# LiDAR_Lite_Interface_CAN.net
KiCad netlist of a schematic drawn in EAGLE
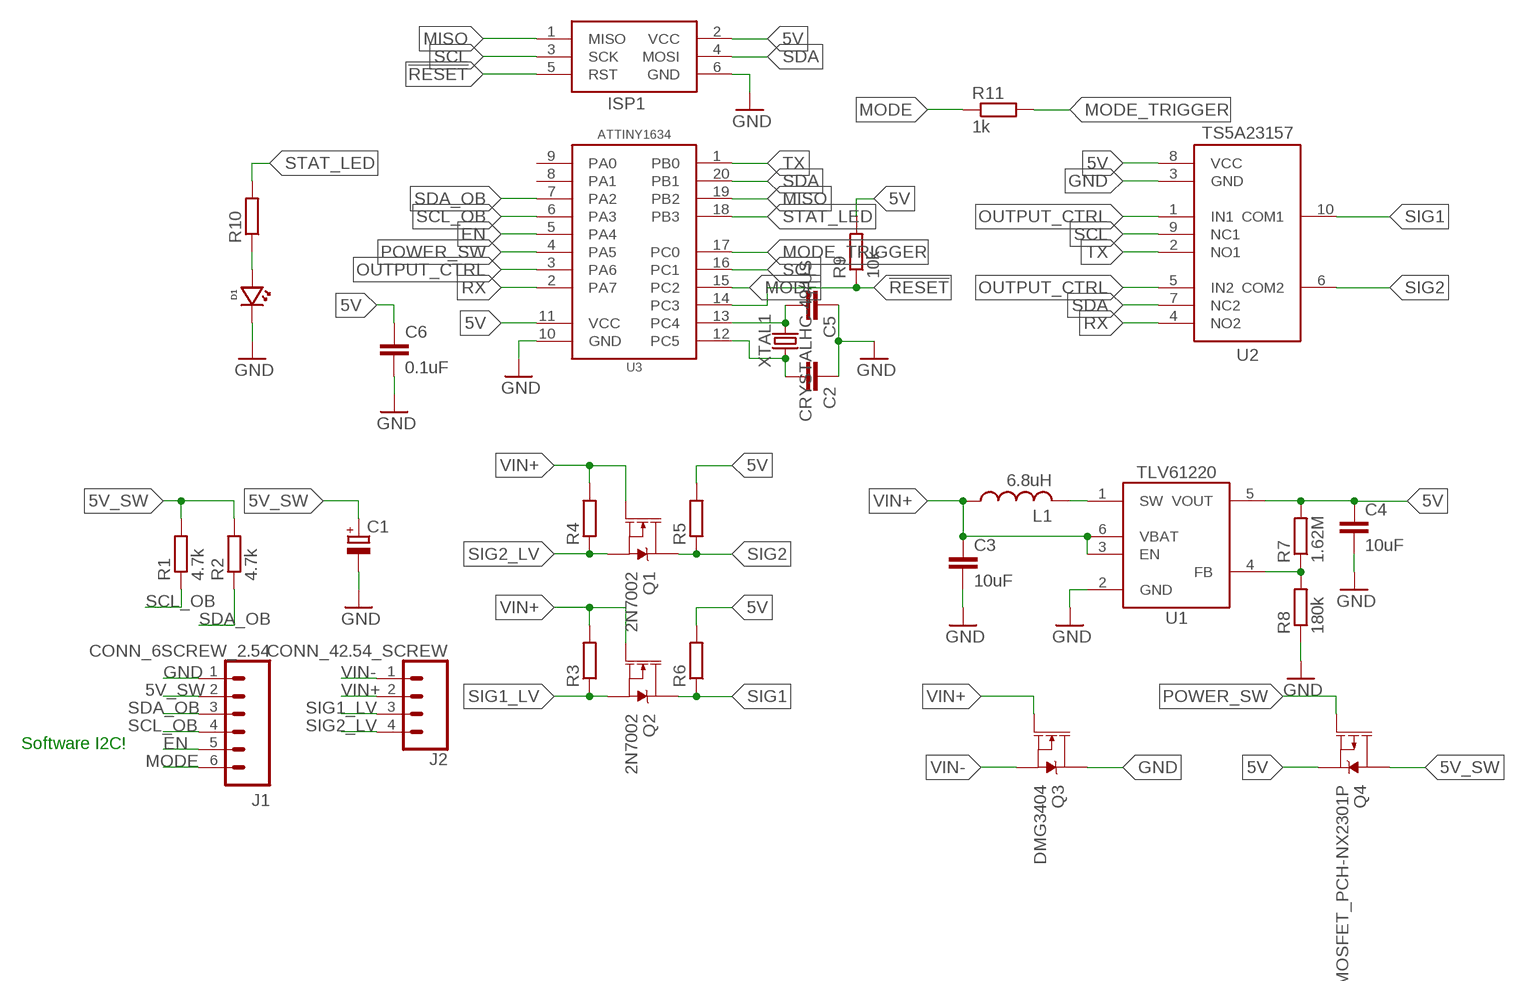
[diagram p0: schematic, sheet 1]

(export (version "E")
  (design (tool "Eeschema 10.0.6"))
  (components
    (comp (ref "C1")
      (value "CPOL-EUUW-10X10")
      (footprint "eagle-import:UW-10X10_NICHICON")
      (libsource (lib "eagle-import") (part "CPOL-EUUW-10X10"))
    )
    (comp (ref "C2")
      (value "C-EU10PFC0603")
      (footprint "eagle-import:C0603")
      (fields (field (name "MF") "Yageo") (field (name "MPN") "CC0603JRNPO9BN100CC0603JRNPO9BN100"))
      (libsource (lib "eagle-import") (part "C-EUC060310PF"))
    )
    (comp (ref "C3")
      (value "10uF")
      (footprint "eagle-import:C0805")
      (fields (field (name "MF") "Murata") (field (name "MPN") "GRM21BR61C106KE15K"))
      (libsource (lib "eagle-import") (part "C-EUC080510UF"))
    )
    (comp (ref "C4")
      (value "10uF")
      (footprint "eagle-import:C0805")
      (fields (field (name "MF") "Murata") (field (name "MPN") "GRM21BR61C106KE15K"))
      (libsource (lib "eagle-import") (part "C-EUC080510UF"))
    )
    (comp (ref "C5")
      (value "C-EU10PFC0603")
      (footprint "eagle-import:C0603")
      (fields (field (name "MF") "Yageo") (field (name "MPN") "CC0603JRNPO9BN100CC0603JRNPO9BN100"))
      (libsource (lib "eagle-import") (part "C-EUC060310PF"))
    )
    (comp (ref "C6")
      (value "0.1uF")
      (footprint "eagle-import:C0603")
      (fields (field (name "MF") "Murata") (field (name "MPN") "GCM188R71E104KA57D"))
      (libsource (lib "eagle-import") (part "C-EUC06030.1UF"))
    )
    (comp (ref "D1")
      (value "LED0603")
      (footprint "eagle-import:LED_0603")
      (libsource (lib "eagle-import") (part "LED0603"))
    )
    (comp (ref "ISP1")
      (value "AVRISP-6")
      (footprint "eagle-import:AVRISP")
      (libsource (lib "eagle-import") (part "AVRISP-6"))
    )
    (comp (ref "J1")
      (value "CONN_6SCREW_2.54")
      (footprint "eagle-import:1X06_SCREW")
      (fields (field (name "MF") "OnShore") (field (name "MPN") "OSTVN06A150"))
      (libsource (lib "eagle-import") (part "CONN_6SCREW_2.54"))
    )
    (comp (ref "J2")
      (value "CONN_42.54_SCREW")
      (footprint "eagle-import:1X04_SCREW")
      (fields (field (name "MF") "On Shore") (field (name "MPN") "OSTVN04A150"))
      (libsource (lib "eagle-import") (part "CONN_42.54_SCREW"))
    )
    (comp (ref "L1")
      (value "6.8uH")
      (footprint "eagle-import:1008")
      (fields (field (name "MF") "Wurth") (field (name "MPN") "74438323068"))
      (libsource (lib "eagle-import") (part "INDUCTOR1008"))
    )
    (comp (ref "Q1")
      (value "2N7002")
      (footprint "eagle-import:SOT23-3")
      (fields (field (name "MF") "Nexperia") (field (name "MPN") "2N7002P,215"))
      (libsource (lib "eagle-import") (part "MOSFET-NCH-2N7002P"))
    )
    (comp (ref "Q2")
      (value "2N7002")
      (footprint "eagle-import:SOT23-3")
      (fields (field (name "MF") "Nexperia") (field (name "MPN") "2N7002P,215"))
      (libsource (lib "eagle-import") (part "MOSFET-NCH-2N7002P"))
    )
    (comp (ref "Q3")
      (value "DMG3404")
      (footprint "eagle-import:SOT23-3")
      (fields (field (name "MF") "Diodes Incorporated") (field (name "MPN") "DMG3404L-7"))
      (libsource (lib "eagle-import") (part "MOSFET-NCH-DMG3404L"))
    )
    (comp (ref "Q4")
      (value "MOSFET_PCH-NX2301P")
      (footprint "eagle-import:SOT23-3")
      (fields (field (name "MF") "Nexperia") (field (name "MPN") "NX2301P,215"))
      (libsource (lib "eagle-import") (part "MOSFET_PCH-NX2301P"))
    )
    (comp (ref "R1")
      (value "4.7k")
      (footprint "eagle-import:R0603")
      (fields (field (name "MF") "Yageo") (field (name "MPN") "RC0603FR-074K7L"))
      (libsource (lib "eagle-import") (part "R-EU_R06034.7K"))
    )
    (comp (ref "R2")
      (value "4.7k")
      (footprint "eagle-import:R0603")
      (fields (field (name "MF") "Yageo") (field (name "MPN") "RC0603FR-074K7L"))
      (libsource (lib "eagle-import") (part "R-EU_R06034.7K"))
    )
    (comp (ref "R3")
      (value "R-EU_10KR0603")
      (footprint "eagle-import:R0603")
      (fields
        (field (name "MF") "Yageo")
        (field (name "MPN") "RC0603FR-0710KL")
        (field (name "VALUE_PART") "10k")
      )
      (libsource (lib "eagle-import") (part "R-EU_R060310K"))
    )
    (comp (ref "R4")
      (value "R-EU_10KR0603")
      (footprint "eagle-import:R0603")
      (fields
        (field (name "MF") "Yageo")
        (field (name "MPN") "RC0603FR-0710KL")
        (field (name "VALUE_PART") "10k")
      )
      (libsource (lib "eagle-import") (part "R-EU_R060310K"))
    )
    (comp (ref "R5")
      (value "R-EU_10KR0603")
      (footprint "eagle-import:R0603")
      (fields
        (field (name "MF") "Yageo")
        (field (name "MPN") "RC0603FR-0710KL")
        (field (name "VALUE_PART") "10k")
      )
      (libsource (lib "eagle-import") (part "R-EU_R060310K"))
    )
    (comp (ref "R6")
      (value "R-EU_10KR0603")
      (footprint "eagle-import:R0603")
      (fields
        (field (name "MF") "Yageo")
        (field (name "MPN") "RC0603FR-0710KL")
        (field (name "VALUE_PART") "10k")
      )
      (libsource (lib "eagle-import") (part "R-EU_R060310K"))
    )
    (comp (ref "R7")
      (value "1.62M")
      (footprint "eagle-import:R0603")
      (fields (field (name "MF") "Stackpole") (field (name "MPN") "RMCF0603FT1M62"))
      (libsource (lib "eagle-import") (part "R-EU_R06031.62M"))
    )
    (comp (ref "R8")
      (value "180k")
      (footprint "eagle-import:R0603")
      (fields (field (name "MF") "Panasonic") (field (name "MPN") "ERJ-3EKF1803V"))
      (libsource (lib "eagle-import") (part "R-EU_R0603180K"))
    )
    (comp (ref "R9")
      (value "10k")
      (footprint "eagle-import:R0603")
      (fields (field (name "MF") "Yageo") (field (name "MPN") "RC0603FR-0710KL"))
      (libsource (lib "eagle-import") (part "R-EU_R060310K"))
    )
    (comp (ref "R10")
      (value "R-EU_330R0603")
      (footprint "eagle-import:R0603")
      (fields
        (field (name "MF") "Yageo")
        (field (name "MPN") "RC0603FR-07330RL")
        (field (name "VALUE_PART") "330")
      )
      (libsource (lib "eagle-import") (part "R-EU_R0603330"))
    )
    (comp (ref "R11")
      (value "1k")
      (footprint "eagle-import:R0603")
      (fields (field (name "MF") "Yageo") (field (name "MPN") "AC0603FR-071KL"))
      (libsource (lib "eagle-import") (part "R-EU_R06031K"))
    )
    (comp (ref "U1")
      (value "TLV61220DBV")
      (footprint "eagle-import:DBV_R-PDSO-G6")
      (fields (field (name "MF") "TI") (field (name "MPN") "TLV61220DBVR"))
      (libsource (lib "eagle-import") (part "TLV61220DBV"))
    )
    (comp (ref "U2")
      (value "TS5A23157DGS")
      (footprint "eagle-import:DGS0010A")
      (fields (field (name "DISP") "TS5A23157") (field (name "MF") "TI") (field (name "MPN") "TS5A23157DGSR"))
      (libsource (lib "eagle-import") (part "TS5A23157DGS"))
    )
    (comp (ref "U3")
      (value "ATTINY1634SOIC")
      (footprint "eagle-import:SO-20DW")
      (fields (field (name "MF") "Atmel") (field (name "MPN") "ATTINY1634-SUR"))
      (libsource (lib "eagle-import") (part "ATTINY1634SOIC"))
    )
    (comp (ref "XTAL1")
      (value "CRYSTALHC-49/US")
      (footprint "eagle-import:HC49UP")
      (libsource (lib "eagle-import") (part "CRYSTALHC-49/US"))
    )
  )
  (nets
    (net (code "1") (name "/~{RESET}") (class "Default")
      (node (ref "ISP1") (pin "5") (pinfunction "RST_5") (pintype "output"))
      (node (ref "R9") (pin "1") (pinfunction "1_1") (pintype "passive"))
      (node (ref "U3") (pin "14") (pinfunction "PC3_14") (pintype "bidirectional"))
    )
    (net (code "2") (name "5V") (class "Default")
      (node (ref "C4") (pin "1") (pinfunction "1_1") (pintype "passive"))
      (node (ref "C6") (pin "1") (pinfunction "1_1") (pintype "passive"))
      (node (ref "ISP1") (pin "2") (pinfunction "VCC_2") (pintype "power_in"))
      (node (ref "Q4") (pin "2") (pinfunction "S_2") (pintype "bidirectional"))
      (node (ref "R5") (pin "2") (pinfunction "2_2") (pintype "passive"))
      (node (ref "R6") (pin "2") (pinfunction "2_2") (pintype "passive"))
      (node (ref "R7") (pin "2") (pinfunction "2_2") (pintype "passive"))
      (node (ref "R9") (pin "2") (pinfunction "2_2") (pintype "passive"))
      (node (ref "U1") (pin "5") (pinfunction "VOUT_5") (pintype "power_in"))
      (node (ref "U2") (pin "8") (pinfunction "VCC_8") (pintype "power_in"))
      (node (ref "U3") (pin "11") (pinfunction "VCC_11") (pintype "power_in"))
    )
    (net (code "3") (name "5V_SW") (class "Default")
      (node (ref "C1") (pin "+") (pinfunction "+_+") (pintype "passive"))
      (node (ref "J1") (pin "2") (pinfunction "2_2") (pintype "passive"))
      (node (ref "Q4") (pin "3") (pinfunction "D_3") (pintype "bidirectional"))
      (node (ref "R1") (pin "2") (pinfunction "2_2") (pintype "passive"))
      (node (ref "R2") (pin "2") (pinfunction "2_2") (pintype "passive"))
    )
    (net (code "4") (name "EN") (class "Default")
      (node (ref "J1") (pin "5") (pinfunction "5_5") (pintype "passive"))
      (node (ref "U3") (pin "5") (pinfunction "PA4_5") (pintype "bidirectional"))
    )
    (net (code "5") (name "GND") (class "Default")
      (node (ref "C1") (pin "-") (pinfunction "-_-") (pintype "passive"))
      (node (ref "C2") (pin "1") (pinfunction "1_1") (pintype "passive"))
      (node (ref "C3") (pin "2") (pinfunction "2_2") (pintype "passive"))
      (node (ref "C4") (pin "2") (pinfunction "2_2") (pintype "passive"))
      (node (ref "C5") (pin "1") (pinfunction "1_1") (pintype "passive"))
      (node (ref "C6") (pin "2") (pinfunction "2_2") (pintype "passive"))
      (node (ref "D1") (pin "CATHODE") (pinfunction "CATHODE_CATHODE") (pintype "power_in"))
      (node (ref "ISP1") (pin "6") (pinfunction "GND_6") (pintype "power_in"))
      (node (ref "J1") (pin "1") (pinfunction "1_1") (pintype "passive"))
      (node (ref "Q3") (pin "3") (pinfunction "D_3") (pintype "bidirectional"))
      (node (ref "R8") (pin "1") (pinfunction "1_1") (pintype "passive"))
      (node (ref "U1") (pin "2") (pinfunction "GND_2") (pintype "power_in"))
      (node (ref "U2") (pin "3") (pinfunction "GND_3") (pintype "power_in"))
      (node (ref "U3") (pin "10") (pinfunction "GND_10") (pintype "power_in"))
    )
    (net (code "6") (name "MISO") (class "Default")
      (node (ref "ISP1") (pin "1") (pinfunction "MISO_1") (pintype "input"))
      (node (ref "U3") (pin "19") (pinfunction "PB2_19") (pintype "bidirectional"))
    )
    (net (code "7") (name "MODE") (class "Default")
      (node (ref "J1") (pin "6") (pinfunction "6_6") (pintype "passive"))
      (node (ref "R11") (pin "1") (pinfunction "1_1") (pintype "passive"))
      (node (ref "U3") (pin "15") (pinfunction "PC2_15") (pintype "bidirectional"))
    )
    (net (code "8") (name "MODE_TRIGGER") (class "Default")
      (node (ref "R11") (pin "2") (pinfunction "2_2") (pintype "passive"))
      (node (ref "U3") (pin "17") (pinfunction "PC0_17") (pintype "bidirectional"))
    )
    (net (code "9") (name "Net-(D1-PadANODE)") (class "Default")
      (node (ref "D1") (pin "ANODE") (pinfunction "ANODE_ANODE") (pintype "power_in"))
      (node (ref "R10") (pin "1") (pinfunction "1_1") (pintype "passive"))
    )
    (net (code "10") (name "Net-(U1-FB)") (class "Default")
      (node (ref "R7") (pin "1") (pinfunction "1_1") (pintype "passive"))
      (node (ref "R8") (pin "2") (pinfunction "2_2") (pintype "passive"))
      (node (ref "U1") (pin "4") (pinfunction "FB_4") (pintype "input"))
    )
    (net (code "11") (name "Net-(U1-SW)") (class "Default")
      (node (ref "L1") (pin "2") (pinfunction "2_2") (pintype "passive"))
      (node (ref "U1") (pin "1") (pinfunction "SW_1") (pintype "power_in"))
    )
    (net (code "12") (name "Net-(U3-PC4)") (class "Default")
      (node (ref "C5") (pin "2") (pinfunction "2_2") (pintype "passive"))
      (node (ref "U3") (pin "13") (pinfunction "PC4_13") (pintype "bidirectional"))
      (node (ref "XTAL1") (pin "2") (pinfunction "2_2") (pintype "passive"))
    )
    (net (code "13") (name "Net-(U3-PC5)") (class "Default")
      (node (ref "C2") (pin "2") (pinfunction "2_2") (pintype "passive"))
      (node (ref "U3") (pin "12") (pinfunction "PC5_12") (pintype "bidirectional"))
      (node (ref "XTAL1") (pin "1") (pinfunction "1_1") (pintype "passive"))
    )
    (net (code "14") (name "OUTPUT_CTRL") (class "Default")
      (node (ref "U2") (pin "1") (pinfunction "IN1_1") (pintype "input"))
      (node (ref "U2") (pin "5") (pinfunction "IN2_5") (pintype "input"))
      (node (ref "U3") (pin "3") (pinfunction "PA6_3") (pintype "bidirectional"))
    )
    (net (code "15") (name "POWER_SW") (class "Default")
      (node (ref "Q4") (pin "1") (pinfunction "G_1") (pintype "bidirectional"))
      (node (ref "U3") (pin "4") (pinfunction "PA5_4") (pintype "bidirectional"))
    )
    (net (code "16") (name "RX") (class "Default")
      (node (ref "U2") (pin "4") (pinfunction "NO2_4") (pintype "bidirectional"))
      (node (ref "U3") (pin "2") (pinfunction "PA7_2") (pintype "bidirectional"))
    )
    (net (code "17") (name "SCL") (class "Default")
      (node (ref "ISP1") (pin "3") (pinfunction "SCK_3") (pintype "output"))
      (node (ref "U2") (pin "9") (pinfunction "NC1_9") (pintype "bidirectional"))
      (node (ref "U3") (pin "16") (pinfunction "PC1_16") (pintype "bidirectional"))
    )
    (net (code "18") (name "SCL_OB") (class "Default")
      (node (ref "J1") (pin "4") (pinfunction "4_4") (pintype "passive"))
      (node (ref "R1") (pin "1") (pinfunction "1_1") (pintype "passive"))
      (node (ref "U3") (pin "6") (pinfunction "PA3_6") (pintype "bidirectional"))
    )
    (net (code "19") (name "SDA") (class "Default")
      (node (ref "ISP1") (pin "4") (pinfunction "MOSI_4") (pintype "output"))
      (node (ref "U2") (pin "7") (pinfunction "NC2_7") (pintype "bidirectional"))
      (node (ref "U3") (pin "20") (pinfunction "PB1_20") (pintype "bidirectional"))
    )
    (net (code "20") (name "SDA_OB") (class "Default")
      (node (ref "J1") (pin "3") (pinfunction "3_3") (pintype "passive"))
      (node (ref "R2") (pin "1") (pinfunction "1_1") (pintype "passive"))
      (node (ref "U3") (pin "7") (pinfunction "PA2_7") (pintype "bidirectional"))
    )
    (net (code "21") (name "SIG1") (class "Default")
      (node (ref "Q2") (pin "3") (pinfunction "D_3") (pintype "bidirectional"))
      (node (ref "R6") (pin "1") (pinfunction "1_1") (pintype "passive"))
      (node (ref "U2") (pin "10") (pinfunction "COM1_10") (pintype "bidirectional"))
    )
    (net (code "22") (name "SIG1_LV") (class "Default")
      (node (ref "J2") (pin "3") (pinfunction "3_3") (pintype "passive"))
      (node (ref "Q2") (pin "2") (pinfunction "S_2") (pintype "bidirectional"))
      (node (ref "R3") (pin "1") (pinfunction "1_1") (pintype "passive"))
    )
    (net (code "23") (name "SIG2") (class "Default")
      (node (ref "Q1") (pin "3") (pinfunction "D_3") (pintype "bidirectional"))
      (node (ref "R5") (pin "1") (pinfunction "1_1") (pintype "passive"))
      (node (ref "U2") (pin "6") (pinfunction "COM2_6") (pintype "bidirectional"))
    )
    (net (code "24") (name "SIG2_LV") (class "Default")
      (node (ref "J2") (pin "4") (pinfunction "4_4") (pintype "passive"))
      (node (ref "Q1") (pin "2") (pinfunction "S_2") (pintype "bidirectional"))
      (node (ref "R4") (pin "1") (pinfunction "1_1") (pintype "passive"))
    )
    (net (code "25") (name "STAT_LED") (class "Default")
      (node (ref "R10") (pin "2") (pinfunction "2_2") (pintype "passive"))
      (node (ref "U3") (pin "18") (pinfunction "PB3_18") (pintype "bidirectional"))
    )
    (net (code "26") (name "TX") (class "Default")
      (node (ref "U2") (pin "2") (pinfunction "NO1_2") (pintype "bidirectional"))
      (node (ref "U3") (pin "1") (pinfunction "PB0_1") (pintype "bidirectional"))
    )
    (net (code "27") (name "VIN+") (class "Default")
      (node (ref "C3") (pin "1") (pinfunction "1_1") (pintype "passive"))
      (node (ref "J2") (pin "2") (pinfunction "2_2") (pintype "passive"))
      (node (ref "L1") (pin "1") (pinfunction "1_1") (pintype "passive"))
      (node (ref "Q1") (pin "1") (pinfunction "G_1") (pintype "bidirectional"))
      (node (ref "Q2") (pin "1") (pinfunction "G_1") (pintype "bidirectional"))
      (node (ref "Q3") (pin "1") (pinfunction "G_1") (pintype "bidirectional"))
      (node (ref "R3") (pin "2") (pinfunction "2_2") (pintype "passive"))
      (node (ref "R4") (pin "2") (pinfunction "2_2") (pintype "passive"))
      (node (ref "U1") (pin "3") (pinfunction "EN_3") (pintype "input"))
      (node (ref "U1") (pin "6") (pinfunction "VBAT_6") (pintype "power_in"))
    )
    (net (code "28") (name "VIN-") (class "Default")
      (node (ref "J2") (pin "1") (pinfunction "1_1") (pintype "passive"))
      (node (ref "Q3") (pin "2") (pinfunction "S_2") (pintype "bidirectional"))
    )
    (net (code "29") (name "unconnected-(U3-PA0-Pad9)") (class "Default")
      (node (ref "U3") (pin "9") (pinfunction "PA0_9") (pintype "bidirectional"))
    )
    (net (code "30") (name "unconnected-(U3-PA1-Pad8)") (class "Default")
      (node (ref "U3") (pin "8") (pinfunction "PA1_8") (pintype "bidirectional"))
    )
  )
)
